# LB-w4-DOUBLE_AND_v03_rev4.net
KiCad netlist of a schematic drawn in EAGLE
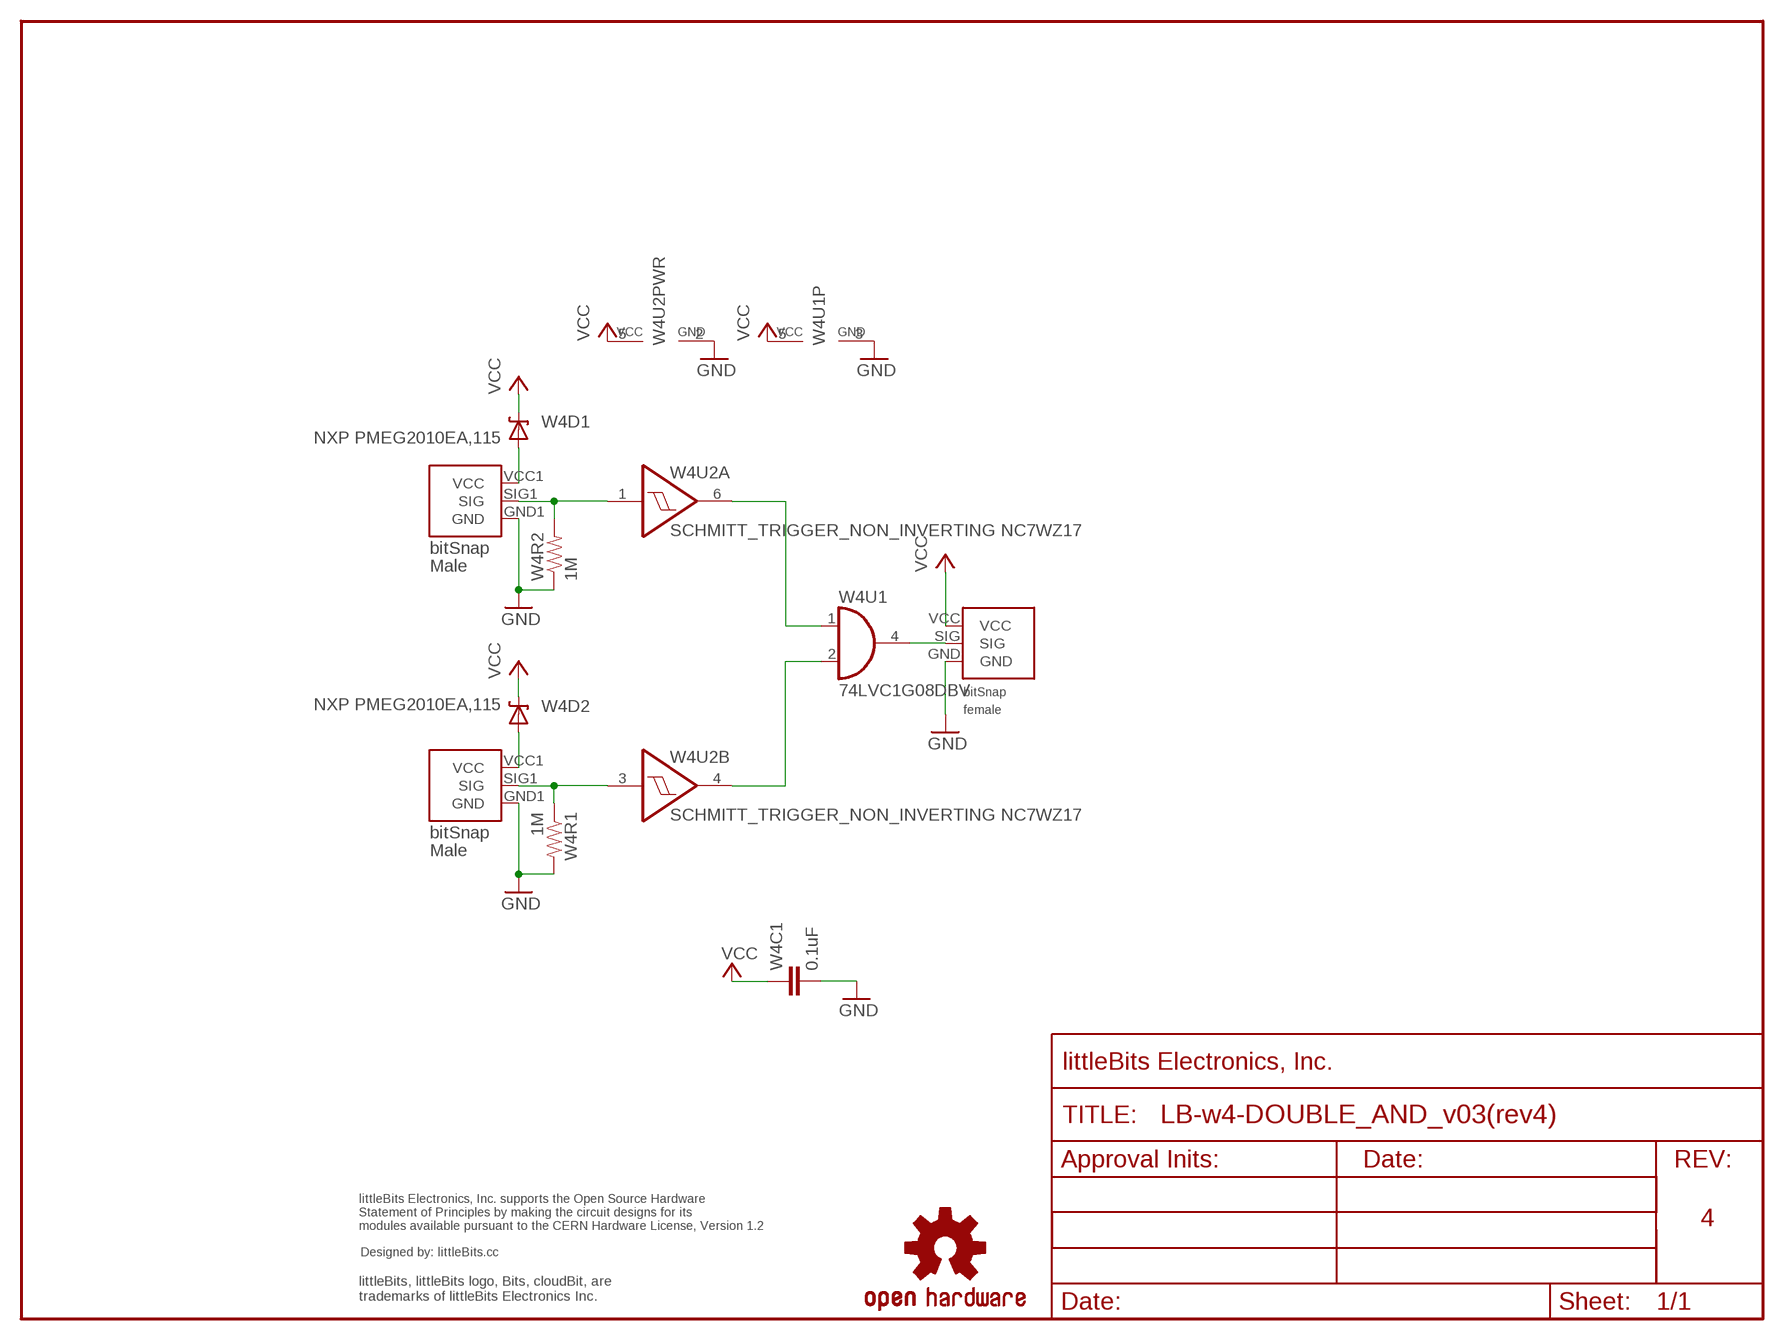
[diagram p0: schematic, sheet 1]

(export (version "E")
  (design (tool "Eeschema 10.0.6"))
  (components
    (comp (ref "FRAME1")
      (value "FRAME-LETTER-OHWOHW")
      (footprint "eagle-import:FABDWG01-OHW")
      (libsource (lib "eagle-import") (part "FRAME-LETTER-OHWOHW"))
    )
    (comp (ref "U$1")
      (value "OSHW-LOGOL")
      (footprint "eagle-import:OSHW-LOGO-L")
      (libsource (lib "eagle-import") (part "OSHW-LOGOL"))
    )
    (comp (ref "U$2")
      (value "OSHWCREDIT")
      (footprint "eagle-import:OSHWCREDIT")
      (libsource (lib "eagle-import") (part "OSHWCREDIT"))
    )
    (comp (ref "W4BSF1")
      (value "BITSNAP_V03_FEMALE")
      (footprint "eagle-import:BITSNAP_V03_FEMALE")
      (libsource (lib "eagle-import") (part "BITSNAP_V03_FEMALE"))
    )
    (comp (ref "W4BSM1")
      (value "BITSNAP_V03_MALE")
      (footprint "eagle-import:BITSNAP_V03_MALE")
      (libsource (lib "eagle-import") (part "BITSNAP_V03_MALE"))
    )
    (comp (ref "W4BSM2")
      (value "BITSNAP_V03_MALE")
      (footprint "eagle-import:BITSNAP_V03_MALE")
      (libsource (lib "eagle-import") (part "BITSNAP_V03_MALE"))
    )
    (comp (ref "W4C1")
      (value "0.1uF")
      (footprint "eagle-import:CAP-0603")
      (libsource (lib "eagle-import") (part "CAPCAP-0603"))
    )
    (comp (ref "W4D1")
      (value "NXP PMEG2010EA,115")
      (footprint "eagle-import:SOD-323")
      (libsource (lib "eagle-import") (part "DIODE-ZENER-BZT52"))
    )
    (comp (ref "W4D2")
      (value "NXP PMEG2010EA,115")
      (footprint "eagle-import:SOD-323")
      (libsource (lib "eagle-import") (part "DIODE-ZENER-BZT52"))
    )
    (comp (ref "W4R1")
      (value "1M")
      (footprint "eagle-import:0603-RES")
      (libsource (lib "eagle-import") (part "RESISTOR0603-RES"))
    )
    (comp (ref "W4R2")
      (value "1M")
      (footprint "eagle-import:0603-RES")
      (libsource (lib "eagle-import") (part "RESISTOR0603-RES"))
    )
    (comp (ref "W4U1")
      (value "74LVC1G08DBV")
      (footprint "eagle-import:SOT23-5")
      (libsource (lib "eagle-import") (part "741G08DBVLVC"))
    )
    (comp (ref "W4U2")
      (value "SCHMITT_TRIGGER_NON_INVERTING NC7WZ17")
      (footprint "eagle-import:SC70-6")
      (libsource (lib "eagle-import") (part "SCHMITT_TRIGGER_NON_INVERTINGNC7WZ17"))
    )
  )
  (nets
    (net (code "1") (name "GND") (class "Default")
      (node (ref "W4BSF1") (pin "GND") (pinfunction "GND_GND") (pintype "bidirectional"))
      (node (ref "W4BSM1") (pin "GND1") (pinfunction "GND_GND1") (pintype "bidirectional"))
      (node (ref "W4BSM2") (pin "GND1") (pinfunction "GND_GND1") (pintype "bidirectional"))
      (node (ref "W4C1") (pin "2") (pinfunction "2_2") (pintype "passive"))
      (node (ref "W4R1") (pin "2") (pinfunction "2_2") (pintype "passive"))
      (node (ref "W4R2") (pin "1") (pinfunction "1_1") (pintype "passive"))
      (node (ref "W4U1") (pin "3") (pinfunction "GND_3") (pintype "power_in"))
      (node (ref "W4U2") (pin "2") (pinfunction "GND_2") (pintype "power_in"))
    )
    (net (code "2") (name "Net-(W4BSM1-SIG)") (class "Default")
      (node (ref "W4BSM1") (pin "SIG1") (pinfunction "SIG_SIG1") (pintype "bidirectional"))
      (node (ref "W4R1") (pin "1") (pinfunction "1_1") (pintype "passive"))
      (node (ref "W4U2") (pin "3") (pinfunction "I_3") (pintype "input"))
    )
    (net (code "3") (name "Net-(W4BSM1-VCC)") (class "Default")
      (node (ref "W4BSM1") (pin "VCC1") (pinfunction "VCC_VCC1") (pintype "bidirectional"))
      (node (ref "W4D2") (pin "2") (pinfunction "A_2") (pintype "passive"))
    )
    (net (code "4") (name "Net-(W4BSM2-SIG)") (class "Default")
      (node (ref "W4BSM2") (pin "SIG1") (pinfunction "SIG_SIG1") (pintype "bidirectional"))
      (node (ref "W4R2") (pin "2") (pinfunction "2_2") (pintype "passive"))
      (node (ref "W4U2") (pin "1") (pinfunction "I_1") (pintype "input"))
    )
    (net (code "5") (name "Net-(W4BSM2-VCC)") (class "Default")
      (node (ref "W4BSM2") (pin "VCC1") (pinfunction "VCC_VCC1") (pintype "bidirectional"))
      (node (ref "W4D1") (pin "2") (pinfunction "A_2") (pintype "passive"))
    )
    (net (code "6") (name "Net-(W4U1A-I0)") (class "Default")
      (node (ref "W4U1") (pin "1") (pinfunction "I0_1") (pintype "input"))
      (node (ref "W4U2") (pin "6") (pinfunction "O_6") (pintype "output"))
    )
    (net (code "7") (name "Net-(W4U1A-I1)") (class "Default")
      (node (ref "W4U1") (pin "2") (pinfunction "I1_2") (pintype "input"))
      (node (ref "W4U2") (pin "4") (pinfunction "O_4") (pintype "output"))
    )
    (net (code "8") (name "Net-(W4U1A-O)") (class "Default")
      (node (ref "W4BSF1") (pin "SIG") (pinfunction "SIG_SIG") (pintype "bidirectional"))
      (node (ref "W4U1") (pin "4") (pinfunction "O_4") (pintype "output"))
    )
    (net (code "9") (name "VCC") (class "Default")
      (node (ref "W4BSF1") (pin "VCC") (pinfunction "VCC_VCC") (pintype "bidirectional"))
      (node (ref "W4C1") (pin "1") (pinfunction "1_1") (pintype "passive"))
      (node (ref "W4D1") (pin "1") (pinfunction "C_1") (pintype "passive"))
      (node (ref "W4D2") (pin "1") (pinfunction "C_1") (pintype "passive"))
      (node (ref "W4U1") (pin "5") (pinfunction "VCC_5") (pintype "power_in"))
      (node (ref "W4U2") (pin "5") (pinfunction "VCC_5") (pintype "power_in"))
    )
  )
)
